# alphanewt_v1_5.net
KiCad netlist of a schematic drawn in EAGLE
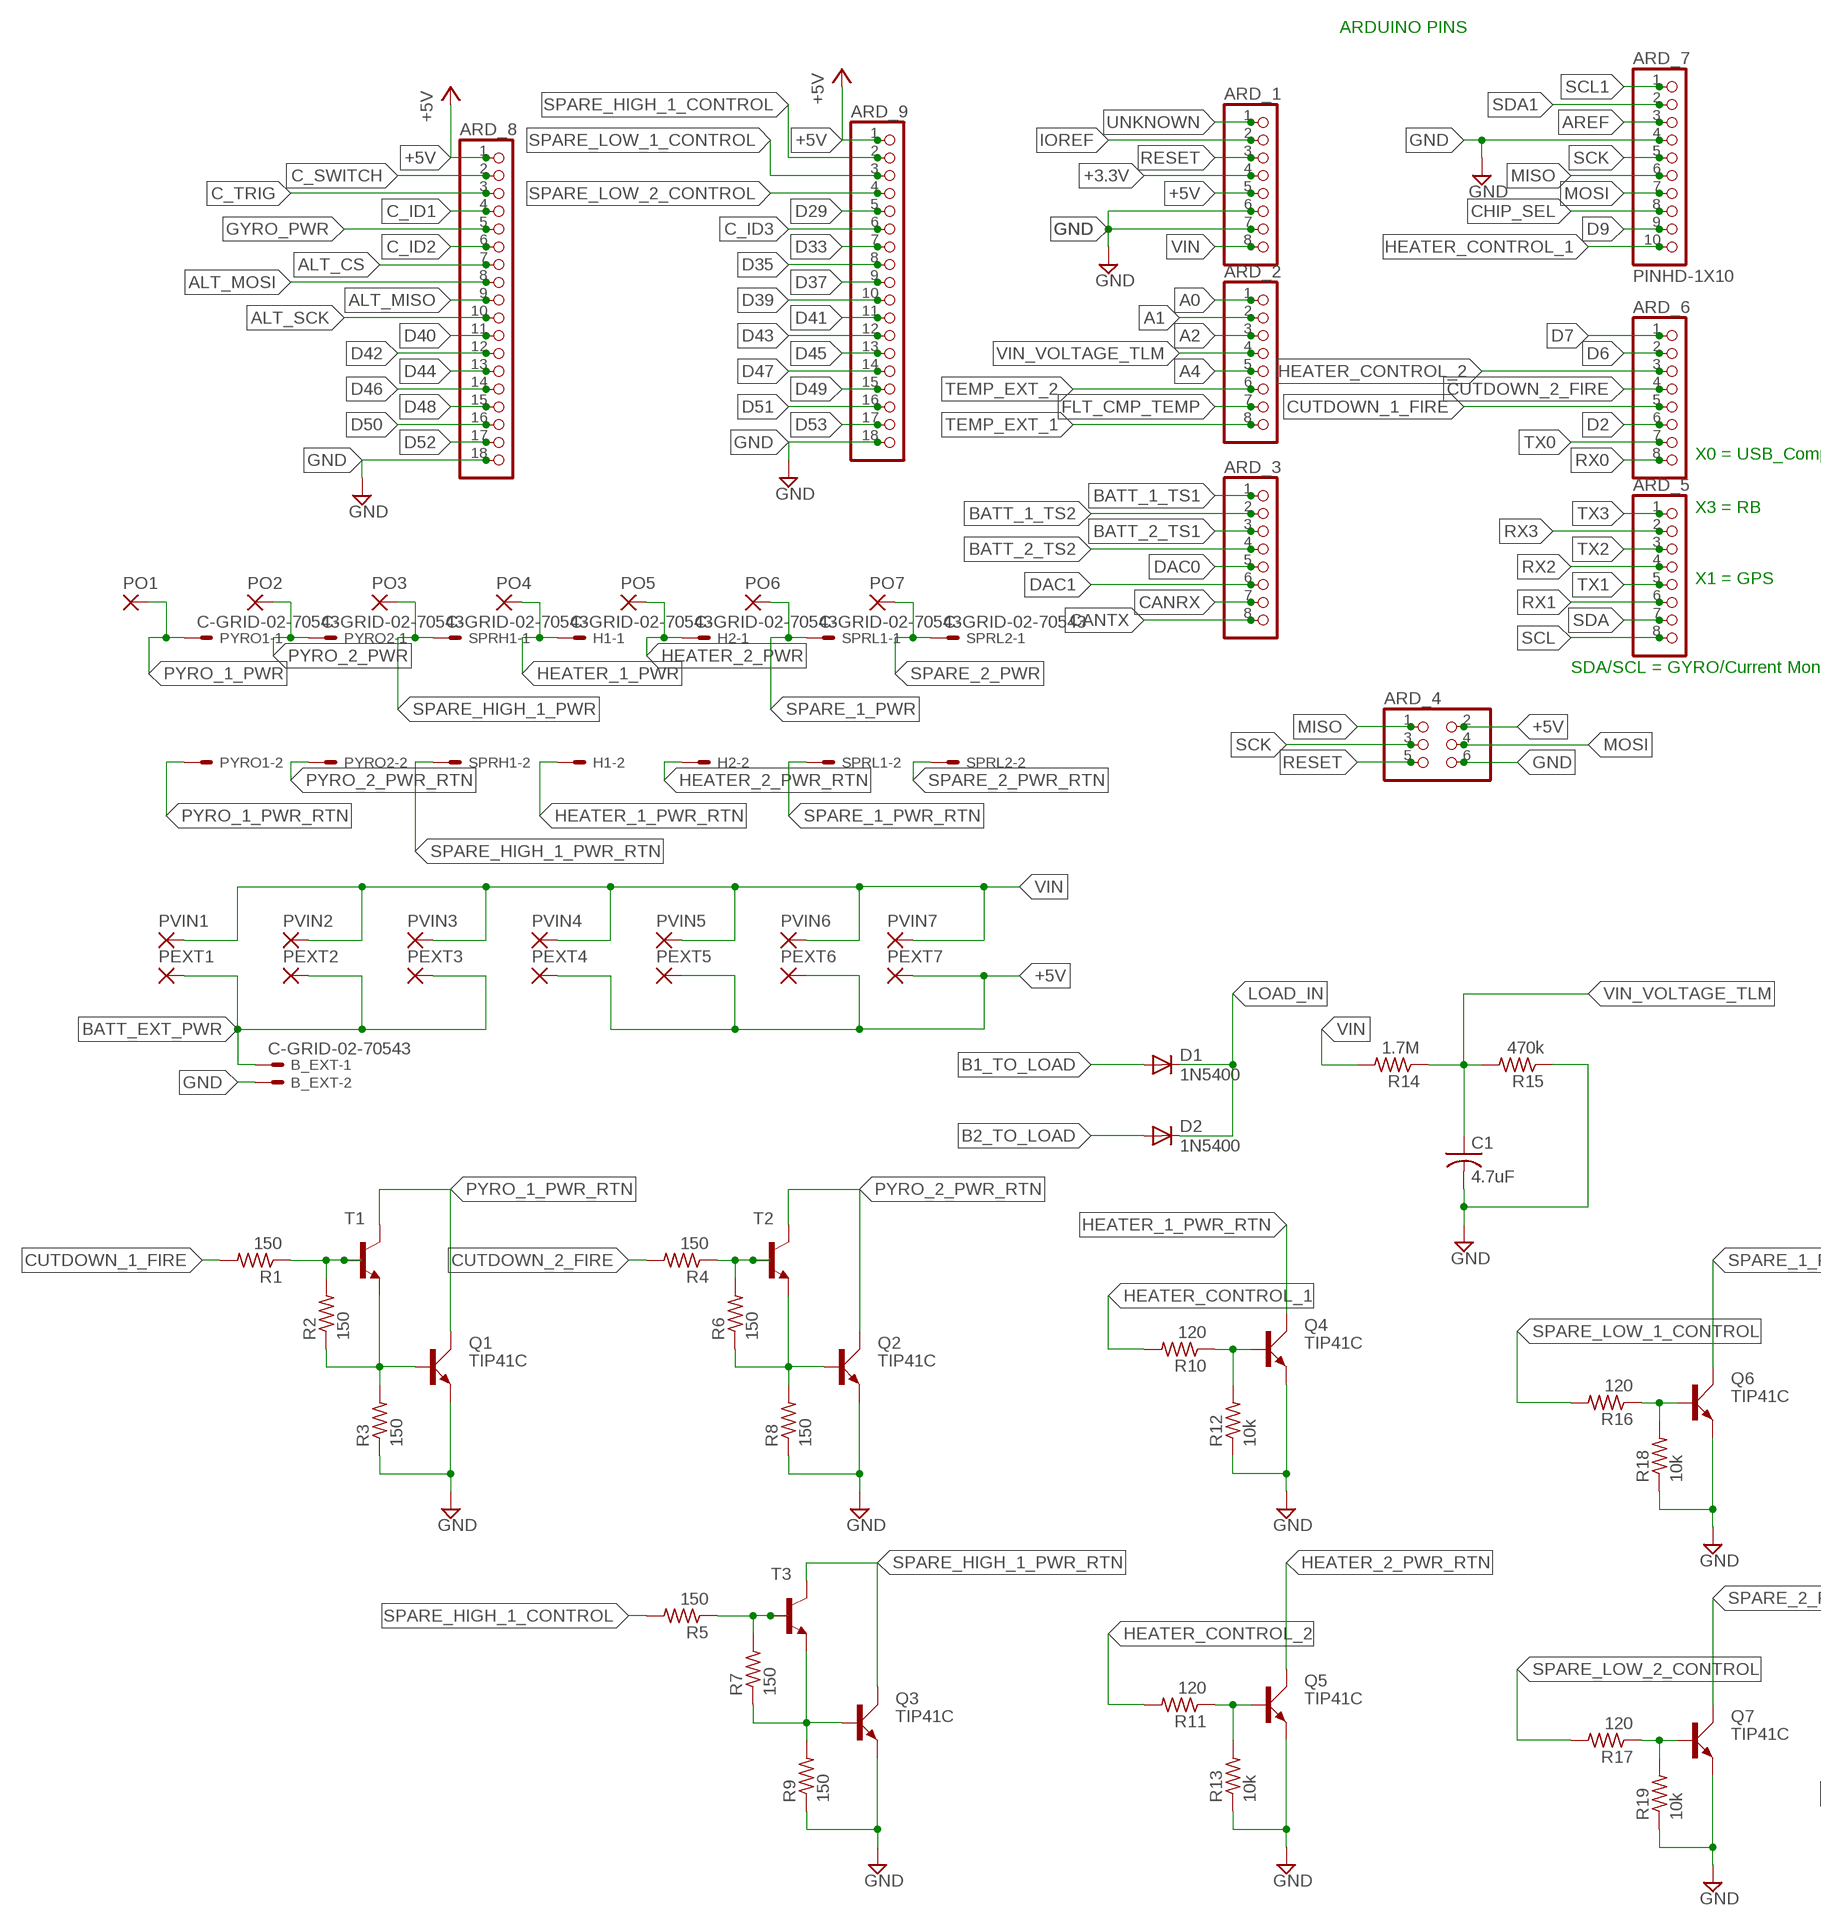
[diagram p0: schematic, sheet 1, part 1 of 2]
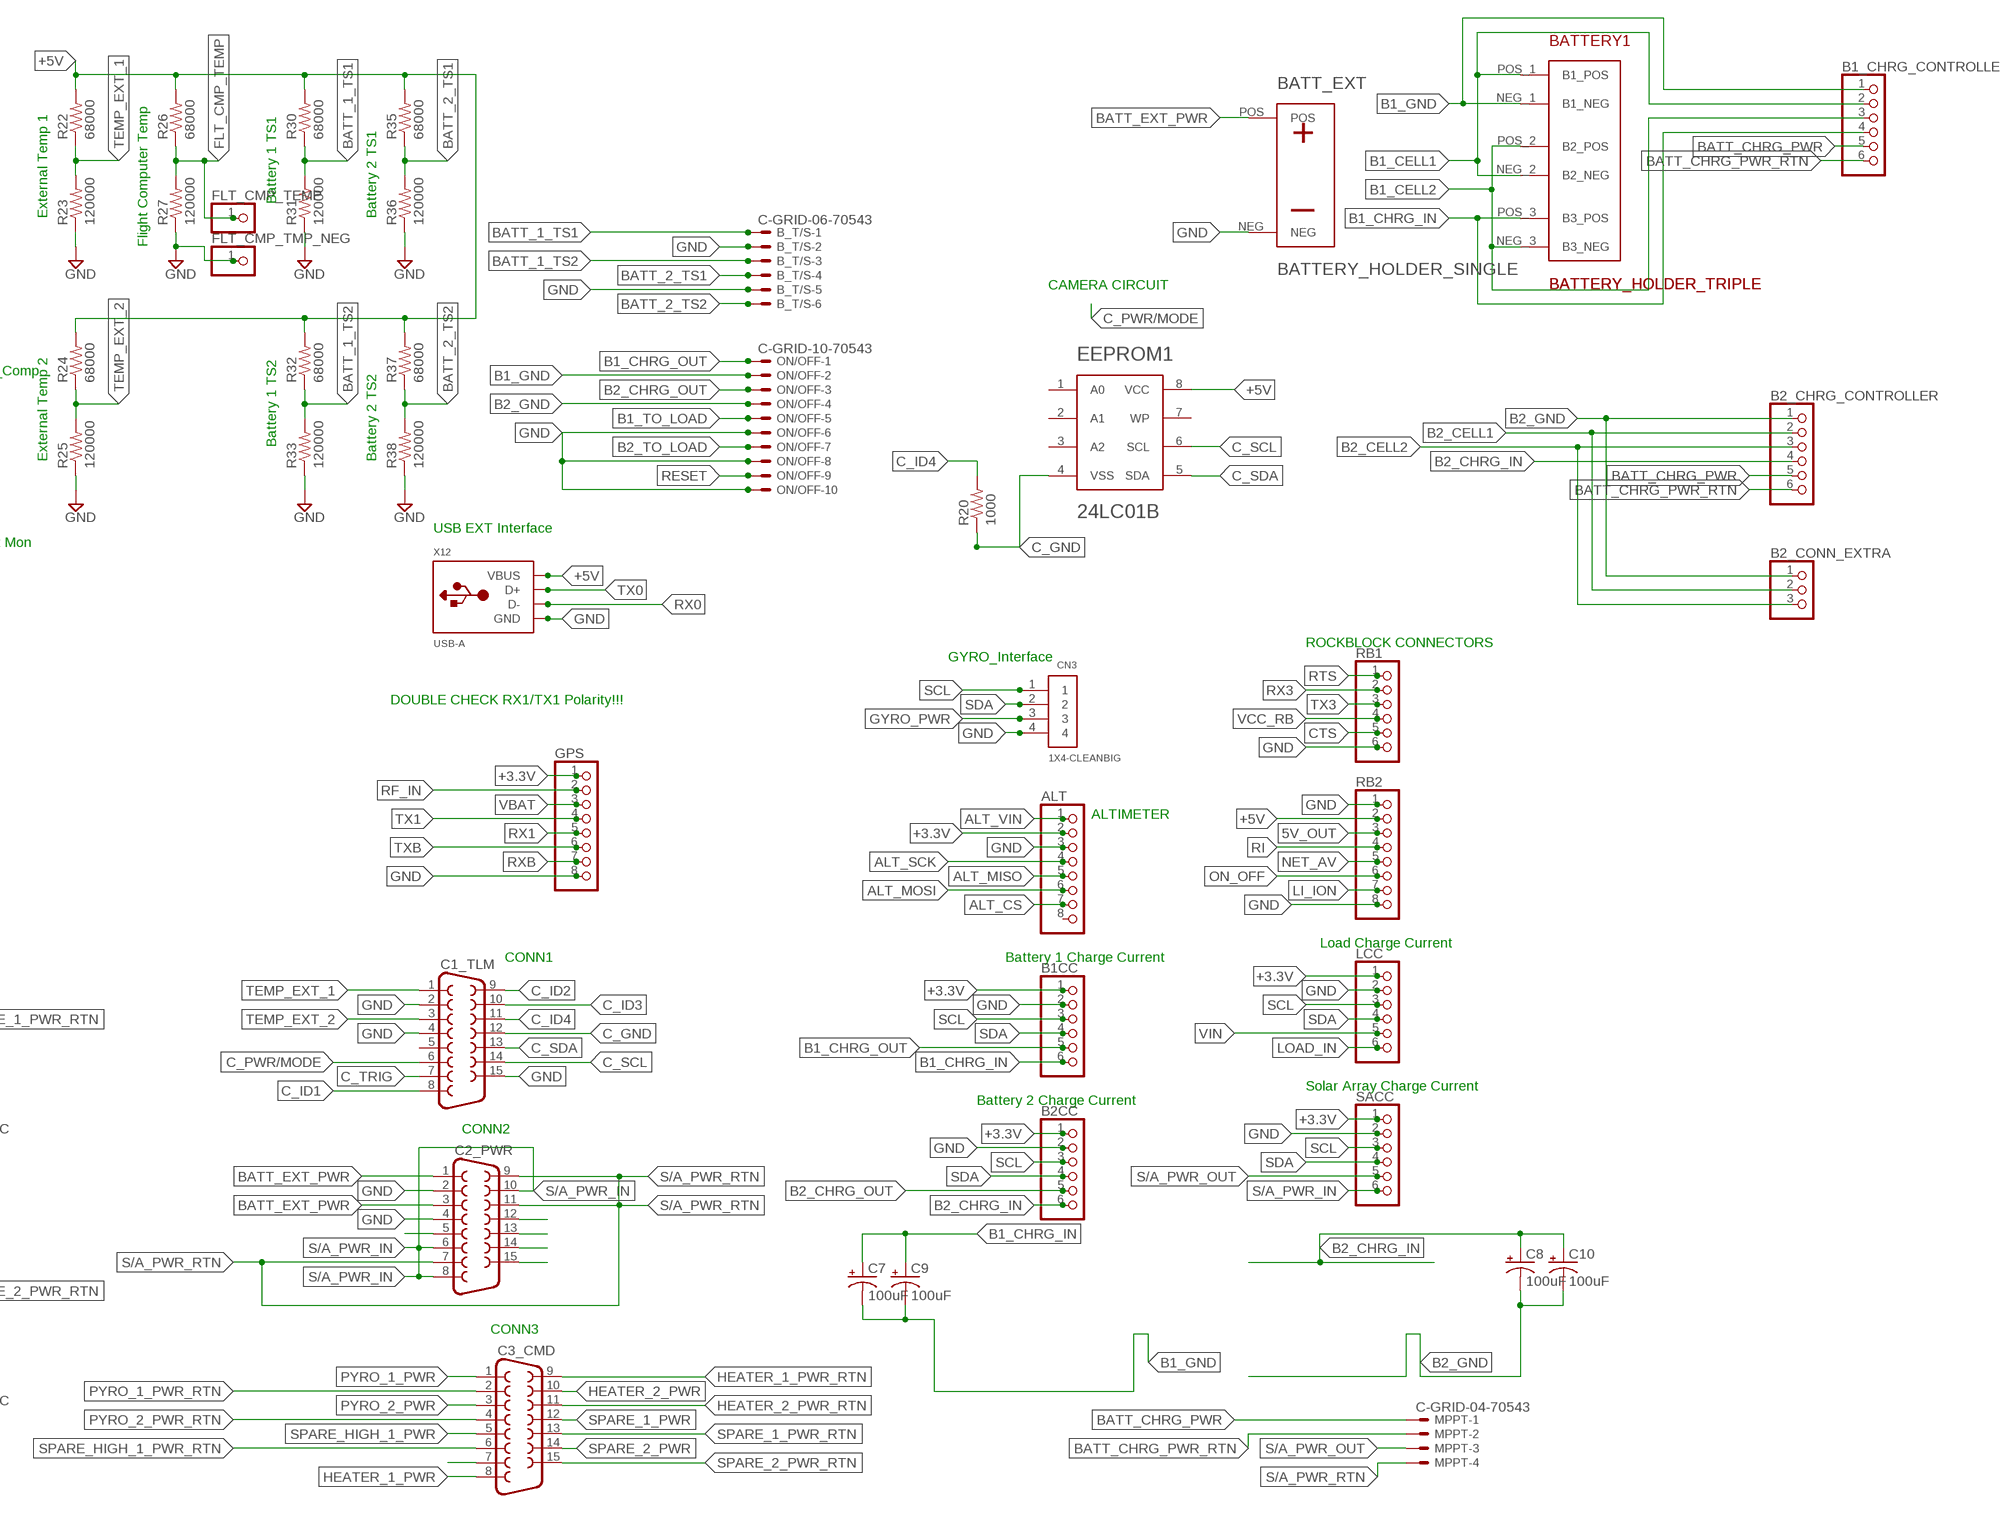
[diagram p1: schematic, sheet 1, part 2 of 2]

(export (version "E")
  (design (tool "Eeschema 10.0.6"))
  (components
    (comp (ref "ALT")
      (value "PINHD-1X8BIG")
      (footprint "eagle-import:1X08-BIG")
      (libsource (lib "eagle-import") (part "PINHD-1X8BIG"))
    )
    (comp (ref "ARD_1")
      (value "PINHD-1X8BIG")
      (footprint "eagle-import:1X08-BIG")
      (libsource (lib "eagle-import") (part "PINHD-1X8BIG"))
    )
    (comp (ref "ARD_2")
      (value "PINHD-1X8BIG")
      (footprint "eagle-import:1X08-BIG")
      (libsource (lib "eagle-import") (part "PINHD-1X8BIG"))
    )
    (comp (ref "ARD_3")
      (value "PINHD-1X8BIG")
      (footprint "eagle-import:1X08-BIG")
      (libsource (lib "eagle-import") (part "PINHD-1X8BIG"))
    )
    (comp (ref "ARD_4")
      (value "PINHD-2X3")
      (footprint "eagle-import:2X03")
      (libsource (lib "eagle-import") (part "PINHD-2X3"))
    )
    (comp (ref "ARD_5")
      (value "PINHD-1X8BIG")
      (footprint "eagle-import:1X08-BIG")
      (libsource (lib "eagle-import") (part "PINHD-1X8BIG"))
    )
    (comp (ref "ARD_6")
      (value "PINHD-1X8BIG")
      (footprint "eagle-import:1X08-BIG")
      (libsource (lib "eagle-import") (part "PINHD-1X8BIG"))
    )
    (comp (ref "ARD_7")
      (value "PINHD-1X10")
      (footprint "eagle-import:1X10-BIG")
      (libsource (lib "eagle-import") (part "PINHD-1X10"))
    )
    (comp (ref "ARD_8")
      (value "PINHD-1X18-BIG")
      (footprint "eagle-import:1X18-BIG")
      (libsource (lib "eagle-import") (part "PINHD-1X18-BIG"))
    )
    (comp (ref "ARD_9")
      (value "PINHD-1X18-BIG")
      (footprint "eagle-import:1X18-BIG")
      (libsource (lib "eagle-import") (part "PINHD-1X18-BIG"))
    )
    (comp (ref "B1CC")
      (value "PINHD-1X6B")
      (footprint "eagle-import:1X06-BIG")
      (libsource (lib "eagle-import") (part "PINHD-1X6B"))
    )
    (comp (ref "B1_CHRG_CONTROLLER")
      (value "PINHD-1X6CLEAN")
      (footprint "eagle-import:1X06-CLEAN")
      (libsource (lib "eagle-import") (part "PINHD-1X6CLEAN"))
    )
    (comp (ref "B2CC")
      (value "PINHD-1X6B")
      (footprint "eagle-import:1X06-BIG")
      (libsource (lib "eagle-import") (part "PINHD-1X6B"))
    )
    (comp (ref "B2_CHRG_CONTROLLER")
      (value "PINHD-1X6CLEAN")
      (footprint "eagle-import:1X06-CLEAN")
      (libsource (lib "eagle-import") (part "PINHD-1X6CLEAN"))
    )
    (comp (ref "B2_CONN_EXTRA")
      (value "PINHD-1X3CB")
      (footprint "eagle-import:1X03-CLEANBIG")
      (libsource (lib "eagle-import") (part "PINHD-1X3CB"))
    )
    (comp (ref "BATTERY1")
      (value "BATTERY_HOLDER_TRIPLE")
      (footprint "eagle-import:BATT_HOLDER_SINGLE")
      (libsource (lib "eagle-import") (part "BATTERY_HOLDER_TRIPLE"))
    )
    (comp (ref "BATT_EXT")
      (value "BATTERY_HOLDER_SINGLE")
      (footprint "eagle-import:BATT_HOLDER_SINGLE")
      (libsource (lib "eagle-import") (part "BATTERY_HOLDER_SINGLE"))
    )
    (comp (ref "B_EXT")
      (value "C-GRID-02-70543")
      (footprint "eagle-import:70543-02")
      (fields
        (field (name "MF") "MOLEX")
        (field (name "MPN") "70543-0001")
        (field (name "OC_NEWARK") "59H2645")
      )
      (libsource (lib "eagle-import") (part "C-GRID-02-70543"))
    )
    (comp (ref "B_T/S")
      (value "C-GRID-06-70543")
      (footprint "eagle-import:70543-06")
      (fields
        (field (name "MF") "MOLEX")
        (field (name "MPN") "70543-0005")
        (field (name "OC_NEWARK") "59H2647")
      )
      (libsource (lib "eagle-import") (part "C-GRID-06-70543"))
    )
    (comp (ref "C1")
      (value "4.7uF")
      (footprint "eagle-import:C0805K")
      (fields (field (name "MPN") "C2012X6S1H475K125AC"))
      (libsource (lib "eagle-import") (part "C-USC0805K"))
    )
    (comp (ref "C1_TLM")
      (value "F15HP")
      (footprint "eagle-import:F15HP")
      (fields (field (name "MPN") "5504F1-15S-02A-03"))
      (libsource (lib "eagle-import") (part "F15HP"))
    )
    (comp (ref "C2_PWR")
      (value "F15HP")
      (footprint "eagle-import:F15HP")
      (fields (field (name "MPN") "5504F1-15S-02A-03"))
      (libsource (lib "eagle-import") (part "F15HP"))
    )
    (comp (ref "C3_CMD")
      (value "F15HP")
      (footprint "eagle-import:F15HP")
      (fields (field (name "MPN") "5504F1-15S-02A-03"))
      (libsource (lib "eagle-import") (part "F15HP"))
    )
    (comp (ref "C7")
      (value "100uF")
      (footprint "eagle-import:CT7343")
      (fields (field (name "MPN") "TCN4337M020R0100"))
      (libsource (lib "eagle-import") (part "CPOL-USCT7343"))
    )
    (comp (ref "C8")
      (value "100uF")
      (footprint "eagle-import:CT7343")
      (fields (field (name "MPN") "TCN4337M020R0100"))
      (libsource (lib "eagle-import") (part "CPOL-USCT7343"))
    )
    (comp (ref "C9")
      (value "100uF")
      (footprint "eagle-import:CT7343")
      (fields (field (name "MPN") "TCN4337M020R0100"))
      (libsource (lib "eagle-import") (part "CPOL-USCT7343"))
    )
    (comp (ref "C10")
      (value "100uF")
      (footprint "eagle-import:CT7343")
      (fields (field (name "MPN") "TCN4337M020R0100"))
      (libsource (lib "eagle-import") (part "CPOL-USCT7343"))
    )
    (comp (ref "CN3")
      (value "1X4-CLEANBIG")
      (footprint "eagle-import:1X04-CLEANBIG")
      (libsource (lib "eagle-import") (part "1X4-CLEANBIG"))
    )
    (comp (ref "D1")
      (value "1N5400")
      (footprint "eagle-import:DO201-15")
      (fields (field (name "MPN") "1N5400-E3/54"))
      (libsource (lib "eagle-import") (part "1N5400"))
    )
    (comp (ref "D2")
      (value "1N5400")
      (footprint "eagle-import:DO201-15")
      (fields (field (name "MPN") "1N5400-E3/54"))
      (libsource (lib "eagle-import") (part "1N5400"))
    )
    (comp (ref "EEPROM1")
      (value "24LC01B")
      (footprint "eagle-import:SOP65P490X110-8N")
      (libsource (lib "eagle-import") (part "24LC01B"))
    )
    (comp (ref "FLT_CMP_TEMP")
      (value "PINHD-1X1")
      (footprint "eagle-import:1X01")
      (libsource (lib "eagle-import") (part "PINHD-1X1"))
    )
    (comp (ref "FLT_CMP_TMP_NEG")
      (value "PINHD-1X1")
      (footprint "eagle-import:1X01")
      (libsource (lib "eagle-import") (part "PINHD-1X1"))
    )
    (comp (ref "GPS")
      (value "PINHD-1X8BIG")
      (footprint "eagle-import:1X08-BIG")
      (libsource (lib "eagle-import") (part "PINHD-1X8BIG"))
    )
    (comp (ref "H1")
      (value "C-GRID-02-70543")
      (footprint "eagle-import:70543-02")
      (fields
        (field (name "MF") "MOLEX")
        (field (name "MPN") "70543-0001")
        (field (name "OC_NEWARK") "59H2645")
      )
      (libsource (lib "eagle-import") (part "C-GRID-02-70543"))
    )
    (comp (ref "H2")
      (value "C-GRID-02-70543")
      (footprint "eagle-import:70543-02")
      (fields
        (field (name "MF") "MOLEX")
        (field (name "MPN") "70543-0001")
        (field (name "OC_NEWARK") "59H2645")
      )
      (libsource (lib "eagle-import") (part "C-GRID-02-70543"))
    )
    (comp (ref "LCC")
      (value "PINHD-1X6B")
      (footprint "eagle-import:1X06-BIG")
      (libsource (lib "eagle-import") (part "PINHD-1X6B"))
    )
    (comp (ref "MPPT")
      (value "C-GRID-04-70543")
      (footprint "eagle-import:70543-04")
      (fields
        (field (name "MF") "MOLEX")
        (field (name "MPN") "70543-0038")
        (field (name "OC_NEWARK") "59H2665")
      )
      (libsource (lib "eagle-import") (part "C-GRID-04-70543"))
    )
    (comp (ref "ON/OFF")
      (value "C-GRID-10-70543")
      (footprint "eagle-import:70543-10")
      (fields
        (field (name "MF") "MOLEX")
        (field (name "MPN") "70543-0009")
        (field (name "OC_NEWARK") "59H2651")
      )
      (libsource (lib "eagle-import") (part "C-GRID-10-70543"))
    )
    (comp (ref "PEXT1")
      (value "SMD2")
      (footprint "eagle-import:SMD1,27-2,54")
      (libsource (lib "eagle-import") (part "SMD2"))
    )
    (comp (ref "PEXT2")
      (value "SMD2")
      (footprint "eagle-import:SMD1,27-2,54")
      (libsource (lib "eagle-import") (part "SMD2"))
    )
    (comp (ref "PEXT3")
      (value "SMD2")
      (footprint "eagle-import:SMD1,27-2,54")
      (libsource (lib "eagle-import") (part "SMD2"))
    )
    (comp (ref "PEXT4")
      (value "SMD2")
      (footprint "eagle-import:SMD1,27-2,54")
      (libsource (lib "eagle-import") (part "SMD2"))
    )
    (comp (ref "PEXT5")
      (value "SMD2")
      (footprint "eagle-import:SMD1,27-2,54")
      (libsource (lib "eagle-import") (part "SMD2"))
    )
    (comp (ref "PEXT6")
      (value "SMD2")
      (footprint "eagle-import:SMD1,27-2,54")
      (libsource (lib "eagle-import") (part "SMD2"))
    )
    (comp (ref "PEXT7")
      (value "SMD2")
      (footprint "eagle-import:SMD1,27-2,54")
      (libsource (lib "eagle-import") (part "SMD2"))
    )
    (comp (ref "PO1")
      (value "SMD2")
      (footprint "eagle-import:SMD1,27-2,54")
      (libsource (lib "eagle-import") (part "SMD2"))
    )
    (comp (ref "PO2")
      (value "SMD2")
      (footprint "eagle-import:SMD1,27-2,54")
      (libsource (lib "eagle-import") (part "SMD2"))
    )
    (comp (ref "PO3")
      (value "SMD2")
      (footprint "eagle-import:SMD1,27-2,54")
      (libsource (lib "eagle-import") (part "SMD2"))
    )
    (comp (ref "PO4")
      (value "SMD2")
      (footprint "eagle-import:SMD1,27-2,54")
      (libsource (lib "eagle-import") (part "SMD2"))
    )
    (comp (ref "PO5")
      (value "SMD2")
      (footprint "eagle-import:SMD1,27-2,54")
      (libsource (lib "eagle-import") (part "SMD2"))
    )
    (comp (ref "PO6")
      (value "SMD2")
      (footprint "eagle-import:SMD1,27-2,54")
      (libsource (lib "eagle-import") (part "SMD2"))
    )
    (comp (ref "PO7")
      (value "SMD2")
      (footprint "eagle-import:SMD1,27-2,54")
      (libsource (lib "eagle-import") (part "SMD2"))
    )
    (comp (ref "PVIN1")
      (value "SMD2")
      (footprint "eagle-import:SMD1,27-2,54")
      (libsource (lib "eagle-import") (part "SMD2"))
    )
    (comp (ref "PVIN2")
      (value "SMD2")
      (footprint "eagle-import:SMD1,27-2,54")
      (libsource (lib "eagle-import") (part "SMD2"))
    )
    (comp (ref "PVIN3")
      (value "SMD2")
      (footprint "eagle-import:SMD1,27-2,54")
      (libsource (lib "eagle-import") (part "SMD2"))
    )
    (comp (ref "PVIN4")
      (value "SMD2")
      (footprint "eagle-import:SMD1,27-2,54")
      (libsource (lib "eagle-import") (part "SMD2"))
    )
    (comp (ref "PVIN5")
      (value "SMD2")
      (footprint "eagle-import:SMD1,27-2,54")
      (libsource (lib "eagle-import") (part "SMD2"))
    )
    (comp (ref "PVIN6")
      (value "SMD2")
      (footprint "eagle-import:SMD1,27-2,54")
      (libsource (lib "eagle-import") (part "SMD2"))
    )
    (comp (ref "PVIN7")
      (value "SMD2")
      (footprint "eagle-import:SMD1,27-2,54")
      (libsource (lib "eagle-import") (part "SMD2"))
    )
    (comp (ref "PYRO1")
      (value "C-GRID-02-70543")
      (footprint "eagle-import:70543-02")
      (fields
        (field (name "MF") "MOLEX")
        (field (name "MPN") "70543-0001")
        (field (name "OC_NEWARK") "59H2645")
      )
      (libsource (lib "eagle-import") (part "C-GRID-02-70543"))
    )
    (comp (ref "PYRO2")
      (value "C-GRID-02-70543")
      (footprint "eagle-import:70543-02")
      (fields
        (field (name "MF") "MOLEX")
        (field (name "MPN") "70543-0001")
        (field (name "OC_NEWARK") "59H2645")
      )
      (libsource (lib "eagle-import") (part "C-GRID-02-70543"))
    )
    (comp (ref "Q1")
      (value "TIP41C")
      (footprint "eagle-import:TO220AV")
      (fields (field (name "MF") "FAIRCHILD SEMICONDUCTOR"))
      (libsource (lib "eagle-import") (part "TIP41C"))
    )
    (comp (ref "Q2")
      (value "TIP41C")
      (footprint "eagle-import:TO220AV")
      (fields (field (name "MF") "FAIRCHILD SEMICONDUCTOR"))
      (libsource (lib "eagle-import") (part "TIP41C"))
    )
    (comp (ref "Q3")
      (value "TIP41C")
      (footprint "eagle-import:TO220AV")
      (fields (field (name "MF") "FAIRCHILD SEMICONDUCTOR"))
      (libsource (lib "eagle-import") (part "TIP41C"))
    )
    (comp (ref "Q4")
      (value "TIP41C")
      (footprint "eagle-import:TO220AV")
      (fields (field (name "MF") "FAIRCHILD SEMICONDUCTOR"))
      (libsource (lib "eagle-import") (part "TIP41C"))
    )
    (comp (ref "Q5")
      (value "TIP41C")
      (footprint "eagle-import:TO220AV")
      (fields (field (name "MF") "FAIRCHILD SEMICONDUCTOR"))
      (libsource (lib "eagle-import") (part "TIP41C"))
    )
    (comp (ref "Q6")
      (value "TIP41C")
      (footprint "eagle-import:TO220AV")
      (fields (field (name "MF") "FAIRCHILD SEMICONDUCTOR"))
      (libsource (lib "eagle-import") (part "TIP41C"))
    )
    (comp (ref "Q7")
      (value "TIP41C")
      (footprint "eagle-import:TO220AV")
      (fields (field (name "MF") "FAIRCHILD SEMICONDUCTOR"))
      (libsource (lib "eagle-import") (part "TIP41C"))
    )
    (comp (ref "R1")
      (value "150")
      (footprint "eagle-import:R0805")
      (fields (field (name "MF") "VISHAY/DALE") (field (name "MPN") "CRCW120633R2FKEA"))
      (libsource (lib "eagle-import") (part "R-US_R0805"))
    )
    (comp (ref "R2")
      (value "150")
      (footprint "eagle-import:R0805")
      (fields (field (name "MF") "VISHAY/DALE") (field (name "MPN") "CRCW120633R2FKEA"))
      (libsource (lib "eagle-import") (part "R-US_R0805"))
    )
    (comp (ref "R3")
      (value "150")
      (footprint "eagle-import:R0805")
      (fields (field (name "MF") "VISHAY/DALE") (field (name "MPN") "CRCW120633R2FKEA"))
      (libsource (lib "eagle-import") (part "R-US_R0805"))
    )
    (comp (ref "R4")
      (value "150")
      (footprint "eagle-import:R0805")
      (fields (field (name "MF") "VISHAY/DALE") (field (name "MPN") "CRCW120633R2FKEA"))
      (libsource (lib "eagle-import") (part "R-US_R0805"))
    )
    (comp (ref "R5")
      (value "150")
      (footprint "eagle-import:R0805")
      (fields (field (name "MF") "VISHAY/DALE") (field (name "MPN") "CRCW120633R2FKEA"))
      (libsource (lib "eagle-import") (part "R-US_R0805"))
    )
    (comp (ref "R6")
      (value "150")
      (footprint "eagle-import:R0805")
      (fields (field (name "MF") "VISHAY/DALE") (field (name "MPN") "CRCW120633R2FKEA"))
      (libsource (lib "eagle-import") (part "R-US_R0805"))
    )
    (comp (ref "R7")
      (value "150")
      (footprint "eagle-import:R0805")
      (fields (field (name "MF") "VISHAY/DALE") (field (name "MPN") "CRCW120633R2FKEA"))
      (libsource (lib "eagle-import") (part "R-US_R0805"))
    )
    (comp (ref "R8")
      (value "150")
      (footprint "eagle-import:R0805")
      (fields (field (name "MF") "VISHAY/DALE") (field (name "MPN") "CRCW120633R2FKEA"))
      (libsource (lib "eagle-import") (part "R-US_R0805"))
    )
    (comp (ref "R9")
      (value "150")
      (footprint "eagle-import:R0805")
      (fields (field (name "MF") "VISHAY/DALE") (field (name "MPN") "CRCW120633R2FKEA"))
      (libsource (lib "eagle-import") (part "R-US_R0805"))
    )
    (comp (ref "R10")
      (value "120")
      (footprint "eagle-import:R0805")
      (fields (field (name "MF") "VISHAY/DALE") (field (name "MPN") "CRCW120633R2FKEA"))
      (libsource (lib "eagle-import") (part "R-US_R0805"))
    )
    (comp (ref "R11")
      (value "120")
      (footprint "eagle-import:R0805")
      (fields (field (name "MF") "VISHAY/DALE") (field (name "MPN") "CRCW120633R2FKEA"))
      (libsource (lib "eagle-import") (part "R-US_R0805"))
    )
    (comp (ref "R12")
      (value "10k")
      (footprint "eagle-import:R0805")
      (fields (field (name "MF") "VISHAY/DALE") (field (name "MPN") "CRCW120633R2FKEA"))
      (libsource (lib "eagle-import") (part "R-US_R0805"))
    )
    (comp (ref "R13")
      (value "10k")
      (footprint "eagle-import:R0805")
      (fields (field (name "MF") "VISHAY/DALE") (field (name "MPN") "CRCW120633R2FKEA"))
      (libsource (lib "eagle-import") (part "R-US_R0805"))
    )
    (comp (ref "R14")
      (value "1.7M")
      (footprint "eagle-import:R0805")
      (fields (field (name "MF") "VISHAY/DALE") (field (name "MPN") "CRCW120633R2FKEA"))
      (libsource (lib "eagle-import") (part "R-US_R0805"))
    )
    (comp (ref "R15")
      (value "470k")
      (footprint "eagle-import:R0805")
      (fields (field (name "MF") "VISHAY/DALE") (field (name "MPN") "CRCW120633R2FKEA"))
      (libsource (lib "eagle-import") (part "R-US_R0805"))
    )
    (comp (ref "R16")
      (value "120")
      (footprint "eagle-import:R0805")
      (fields (field (name "MF") "VISHAY/DALE") (field (name "MPN") "CRCW120633R2FKEA"))
      (libsource (lib "eagle-import") (part "R-US_R0805"))
    )
    (comp (ref "R17")
      (value "120")
      (footprint "eagle-import:R0805")
      (fields (field (name "MF") "VISHAY/DALE") (field (name "MPN") "CRCW120633R2FKEA"))
      (libsource (lib "eagle-import") (part "R-US_R0805"))
    )
    (comp (ref "R18")
      (value "10k")
      (footprint "eagle-import:R0805")
      (fields (field (name "MF") "VISHAY/DALE") (field (name "MPN") "CRCW120633R2FKEA"))
      (libsource (lib "eagle-import") (part "R-US_R0805"))
    )
    (comp (ref "R19")
      (value "10k")
      (footprint "eagle-import:R0805")
      (fields (field (name "MF") "VISHAY/DALE") (field (name "MPN") "CRCW120633R2FKEA"))
      (libsource (lib "eagle-import") (part "R-US_R0805"))
    )
    (comp (ref "R20")
      (value "1000")
      (footprint "eagle-import:R0805")
      (fields (field (name "MF") "VISHAY/DALE") (field (name "MPN") "CRCW120633R2FKEA"))
      (libsource (lib "eagle-import") (part "R-US_R0805"))
    )
    (comp (ref "R22")
      (value "68000")
      (footprint "eagle-import:R0805")
      (fields (field (name "MF") "VISHAY/DALE") (field (name "MPN") "CRCW120633R2FKEA"))
      (libsource (lib "eagle-import") (part "R-US_R0805"))
    )
    (comp (ref "R23")
      (value "120000")
      (footprint "eagle-import:R0805")
      (fields (field (name "MF") "VISHAY/DALE") (field (name "MPN") "CRCW120633R2FKEA"))
      (libsource (lib "eagle-import") (part "R-US_R0805"))
    )
    (comp (ref "R24")
      (value "68000")
      (footprint "eagle-import:R0805")
      (fields (field (name "MF") "VISHAY/DALE") (field (name "MPN") "CRCW120633R2FKEA"))
      (libsource (lib "eagle-import") (part "R-US_R0805"))
    )
    (comp (ref "R25")
      (value "120000")
      (footprint "eagle-import:R0805")
      (fields (field (name "MF") "VISHAY/DALE") (field (name "MPN") "CRCW120633R2FKEA"))
      (libsource (lib "eagle-import") (part "R-US_R0805"))
    )
    (comp (ref "R26")
      (value "68000")
      (footprint "eagle-import:R0805")
      (fields (field (name "MF") "VISHAY/DALE") (field (name "MPN") "CRCW120633R2FKEA"))
      (libsource (lib "eagle-import") (part "R-US_R0805"))
    )
    (comp (ref "R27")
      (value "120000")
      (footprint "eagle-import:R0805")
      (fields (field (name "MF") "VISHAY/DALE") (field (name "MPN") "CRCW120633R2FKEA"))
      (libsource (lib "eagle-import") (part "R-US_R0805"))
    )
    (comp (ref "R30")
      (value "68000")
      (footprint "eagle-import:R0805")
      (fields (field (name "MF") "VISHAY/DALE") (field (name "MPN") "CRCW120633R2FKEA"))
      (libsource (lib "eagle-import") (part "R-US_R0805"))
    )
    (comp (ref "R31")
      (value "120000")
      (footprint "eagle-import:R0805")
      (fields (field (name "MF") "VISHAY/DALE") (field (name "MPN") "CRCW120633R2FKEA"))
      (libsource (lib "eagle-import") (part "R-US_R0805"))
    )
    (comp (ref "R32")
      (value "68000")
      (footprint "eagle-import:R0805")
      (fields (field (name "MF") "VISHAY/DALE") (field (name "MPN") "CRCW120633R2FKEA"))
      (libsource (lib "eagle-import") (part "R-US_R0805"))
    )
    (comp (ref "R33")
      (value "120000")
      (footprint "eagle-import:R0805")
      (fields (field (name "MF") "VISHAY/DALE") (field (name "MPN") "CRCW120633R2FKEA"))
      (libsource (lib "eagle-import") (part "R-US_R0805"))
    )
    (comp (ref "R35")
      (value "68000")
      (footprint "eagle-import:R0805")
      (fields (field (name "MF") "VISHAY/DALE") (field (name "MPN") "CRCW120633R2FKEA"))
      (libsource (lib "eagle-import") (part "R-US_R0805"))
    )
    (comp (ref "R36")
      (value "120000")
      (footprint "eagle-import:R0805")
      (fields (field (name "MF") "VISHAY/DALE") (field (name "MPN") "CRCW120633R2FKEA"))
      (libsource (lib "eagle-import") (part "R-US_R0805"))
    )
    (comp (ref "R37")
      (value "68000")
      (footprint "eagle-import:R0805")
      (fields (field (name "MF") "VISHAY/DALE") (field (name "MPN") "CRCW120633R2FKEA"))
      (libsource (lib "eagle-import") (part "R-US_R0805"))
    )
    (comp (ref "R38")
      (value "120000")
      (footprint "eagle-import:R0805")
      (fields (field (name "MF") "VISHAY/DALE") (field (name "MPN") "CRCW120633R2FKEA"))
      (libsource (lib "eagle-import") (part "R-US_R0805"))
    )
    (comp (ref "RB1")
      (value "PINHD-1X6CB")
      (footprint "eagle-import:1X06-CLEANBIG")
      (libsource (lib "eagle-import") (part "PINHD-1X6CB"))
    )
    (comp (ref "RB2")
      (value "PINHD-1X8BIG")
      (footprint "eagle-import:1X08-BIG")
      (libsource (lib "eagle-import") (part "PINHD-1X8BIG"))
    )
    (comp (ref "SACC")
      (value "PINHD-1X6B")
      (footprint "eagle-import:1X06-BIG")
      (libsource (lib "eagle-import") (part "PINHD-1X6B"))
    )
    (comp (ref "SPRH1")
      (value "C-GRID-02-70543")
      (footprint "eagle-import:70543-02")
      (fields
        (field (name "MF") "MOLEX")
        (field (name "MPN") "70543-0001")
        (field (name "OC_NEWARK") "59H2645")
      )
      (libsource (lib "eagle-import") (part "C-GRID-02-70543"))
    )
    (comp (ref "SPRL1")
      (value "C-GRID-02-70543")
      (footprint "eagle-import:70543-02")
      (fields
        (field (name "MF") "MOLEX")
        (field (name "MPN") "70543-0001")
        (field (name "OC_NEWARK") "59H2645")
      )
      (libsource (lib "eagle-import") (part "C-GRID-02-70543"))
    )
    (comp (ref "SPRL2")
      (value "C-GRID-02-70543")
      (footprint "eagle-import:70543-02")
      (fields
        (field (name "MF") "MOLEX")
        (field (name "MPN") "70543-0001")
        (field (name "OC_NEWARK") "59H2645")
      )
      (libsource (lib "eagle-import") (part "C-GRID-02-70543"))
    )
    (comp (ref "T1")
      (value "2N3904")
      (footprint "eagle-import:TO92")
      (fields (field (name "MF") "NTE ELECTRONICS"))
      (libsource (lib "eagle-import") (part "2N3904"))
    )
    (comp (ref "T2")
      (value "2N3904")
      (footprint "eagle-import:TO92")
      (fields (field (name "MF") "NTE ELECTRONICS"))
      (libsource (lib "eagle-import") (part "2N3904"))
    )
    (comp (ref "T3")
      (value "2N3904")
      (footprint "eagle-import:TO92")
      (fields (field (name "MF") "NTE ELECTRONICS"))
      (libsource (lib "eagle-import") (part "2N3904"))
    )
    (comp (ref "X12")
      (value "USB-A")
      (footprint "eagle-import:MOLEX_480371000")
      (fields (field (name "MPN") "UE27-AC54-10H"))
      (libsource (lib "eagle-import") (part "USB-A"))
    )
  )
  (nets
    (net (code "1") (name "+3.3V") (class "Default")
      (node (ref "ALT") (pin "2") (pinfunction "2_2") (pintype "passive"))
      (node (ref "ARD_1") (pin "4") (pinfunction "4_4") (pintype "passive"))
      (node (ref "B1CC") (pin "1") (pinfunction "1_1") (pintype "passive"))
      (node (ref "B2CC") (pin "1") (pinfunction "1_1") (pintype "passive"))
      (node (ref "GPS") (pin "1") (pinfunction "1_1") (pintype "passive"))
      (node (ref "LCC") (pin "1") (pinfunction "1_1") (pintype "passive"))
      (node (ref "SACC") (pin "1") (pinfunction "1_1") (pintype "passive"))
    )
    (net (code "2") (name "+5V") (class "Default")
      (node (ref "ARD_1") (pin "5") (pinfunction "5_5") (pintype "passive"))
      (node (ref "ARD_4") (pin "2") (pinfunction "2_2") (pintype "passive"))
      (node (ref "ARD_8") (pin "1") (pinfunction "1_1") (pintype "passive"))
      (node (ref "ARD_9") (pin "1") (pinfunction "1_1") (pintype "passive"))
      (node (ref "EEPROM1") (pin "8") (pinfunction "VCC_8") (pintype "bidirectional"))
      (node (ref "PEXT4") (pin "1") (pinfunction "P_1") (pintype "passive"))
      (node (ref "PEXT5") (pin "1") (pinfunction "P_1") (pintype "passive"))
      (node (ref "PEXT6") (pin "1") (pinfunction "P_1") (pintype "passive"))
      (node (ref "PEXT7") (pin "1") (pinfunction "P_1") (pintype "passive"))
      (node (ref "R22") (pin "2") (pinfunction "2_2") (pintype "passive"))
      (node (ref "R24") (pin "2") (pinfunction "2_2") (pintype "passive"))
      (node (ref "R26") (pin "2") (pinfunction "2_2") (pintype "passive"))
      (node (ref "R30") (pin "2") (pinfunction "2_2") (pintype "passive"))
      (node (ref "R32") (pin "2") (pinfunction "2_2") (pintype "passive"))
      (node (ref "R35") (pin "2") (pinfunction "2_2") (pintype "passive"))
      (node (ref "R37") (pin "2") (pinfunction "2_2") (pintype "passive"))
      (node (ref "RB2") (pin "2") (pinfunction "2_2") (pintype "passive"))
      (node (ref "X12") (pin "1") (pinfunction "VBUS_1") (pintype "power_in"))
    )
    (net (code "3") (name "5V_OUT") (class "Default")
      (node (ref "RB2") (pin "3") (pinfunction "3_3") (pintype "passive"))
    )
    (net (code "4") (name "A0") (class "Default")
      (node (ref "ARD_2") (pin "1") (pinfunction "1_1") (pintype "passive"))
    )
    (net (code "5") (name "A1") (class "Default")
      (node (ref "ARD_2") (pin "2") (pinfunction "2_2") (pintype "passive"))
    )
    (net (code "6") (name "A2") (class "Default")
      (node (ref "ARD_2") (pin "3") (pinfunction "3_3") (pintype "passive"))
    )
    (net (code "7") (name "A4") (class "Default")
      (node (ref "ARD_2") (pin "5") (pinfunction "5_5") (pintype "passive"))
    )
    (net (code "8") (name "ALT_CS") (class "Default")
      (node (ref "ALT") (pin "7") (pinfunction "7_7") (pintype "passive"))
      (node (ref "ARD_8") (pin "7") (pinfunction "7_7") (pintype "passive"))
    )
    (net (code "9") (name "ALT_MISO") (class "Default")
      (node (ref "ALT") (pin "5") (pinfunction "5_5") (pintype "passive"))
      (node (ref "ARD_8") (pin "9") (pinfunction "9_9") (pintype "passive"))
    )
    (net (code "10") (name "ALT_MOSI") (class "Default")
      (node (ref "ALT") (pin "6") (pinfunction "6_6") (pintype "passive"))
      (node (ref "ARD_8") (pin "8") (pinfunction "8_8") (pintype "passive"))
    )
    (net (code "11") (name "ALT_SCK") (class "Default")
      (node (ref "ALT") (pin "4") (pinfunction "4_4") (pintype "passive"))
      (node (ref "ARD_8") (pin "10") (pinfunction "10_10") (pintype "passive"))
    )
    (net (code "12") (name "ALT_VIN") (class "Default")
      (node (ref "ALT") (pin "1") (pinfunction "1_1") (pintype "passive"))
    )
    (net (code "13") (name "AREF") (class "Default")
      (node (ref "ARD_7") (pin "3") (pinfunction "3_3") (pintype "passive"))
    )
    (net (code "14") (name "B1_CELL1") (class "Default")
      (node (ref "B1_CHRG_CONTROLLER") (pin "2") (pinfunction "2_2") (pintype "passive"))
      (node (ref "BATTERY1") (pin "NEG_2") (pinfunction "B2_NEG_NEG_2") (pintype "bidirectional"))
      (node (ref "BATTERY1") (pin "POS_1") (pinfunction "B1_POS_POS_1") (pintype "bidirectional"))
    )
    (net (code "15") (name "B1_CELL2") (class "Default")
      (node (ref "B1_CHRG_CONTROLLER") (pin "3") (pinfunction "3_3") (pintype "passive"))
      (node (ref "BATTERY1") (pin "NEG_3") (pinfunction "B3_NEG_NEG_3") (pintype "bidirectional"))
      (node (ref "BATTERY1") (pin "POS_2") (pinfunction "B2_POS_POS_2") (pintype "bidirectional"))
    )
    (net (code "16") (name "B1_CHRG_IN") (class "Default")
      (node (ref "B1CC") (pin "6") (pinfunction "6_6") (pintype "passive"))
      (node (ref "B1_CHRG_CONTROLLER") (pin "4") (pinfunction "4_4") (pintype "passive"))
      (node (ref "BATTERY1") (pin "POS_3") (pinfunction "B3_POS_POS_3") (pintype "bidirectional"))
      (node (ref "C7") (pin "+") (pinfunction "+_+") (pintype "passive"))
      (node (ref "C9") (pin "+") (pinfunction "+_+") (pintype "passive"))
    )
    (net (code "17") (name "B1_CHRG_OUT") (class "Default")
      (node (ref "B1CC") (pin "5") (pinfunction "5_5") (pintype "passive"))
      (node (ref "ON/OFF") (pin "1") (pinfunction "S_1") (pintype "passive"))
    )
    (net (code "18") (name "B1_GND") (class "Default")
      (node (ref "B1_CHRG_CONTROLLER") (pin "1") (pinfunction "1_1") (pintype "passive"))
      (node (ref "BATTERY1") (pin "NEG_1") (pinfunction "B1_NEG_NEG_1") (pintype "bidirectional"))
      (node (ref "C7") (pin "-") (pinfunction "-_-") (pintype "passive"))
      (node (ref "C9") (pin "-") (pinfunction "-_-") (pintype "passive"))
      (node (ref "ON/OFF") (pin "2") (pinfunction "S_2") (pintype "passive"))
    )
    (net (code "19") (name "B1_TO_LOAD") (class "Default")
      (node (ref "D1") (pin "A") (pinfunction "A_A") (pintype "passive"))
      (node (ref "ON/OFF") (pin "5") (pinfunction "S_5") (pintype "passive"))
    )
    (net (code "20") (name "B2_CELL1") (class "Default")
      (node (ref "B2_CHRG_CONTROLLER") (pin "2") (pinfunction "2_2") (pintype "passive"))
      (node (ref "B2_CONN_EXTRA") (pin "2") (pinfunction "2_2") (pintype "passive"))
    )
    (net (code "21") (name "B2_CELL2") (class "Default")
      (node (ref "B2_CHRG_CONTROLLER") (pin "3") (pinfunction "3_3") (pintype "passive"))
      (node (ref "B2_CONN_EXTRA") (pin "3") (pinfunction "3_3") (pintype "passive"))
    )
    (net (code "22") (name "B2_CHRG_IN") (class "Default")
      (node (ref "B2CC") (pin "6") (pinfunction "6_6") (pintype "passive"))
      (node (ref "B2_CHRG_CONTROLLER") (pin "4") (pinfunction "4_4") (pintype "passive"))
      (node (ref "C10") (pin "+") (pinfunction "+_+") (pintype "passive"))
      (node (ref "C8") (pin "+") (pinfunction "+_+") (pintype "passive"))
    )
    (net (code "23") (name "B2_CHRG_OUT") (class "Default")
      (node (ref "B2CC") (pin "5") (pinfunction "5_5") (pintype "passive"))
      (node (ref "ON/OFF") (pin "3") (pinfunction "S_3") (pintype "passive"))
    )
    (net (code "24") (name "B2_GND") (class "Default")
      (node (ref "B2_CHRG_CONTROLLER") (pin "1") (pinfunction "1_1") (pintype "passive"))
      (node (ref "B2_CONN_EXTRA") (pin "1") (pinfunction "1_1") (pintype "passive"))
      (node (ref "C10") (pin "-") (pinfunction "-_-") (pintype "passive"))
      (node (ref "C8") (pin "-") (pinfunction "-_-") (pintype "passive"))
      (node (ref "ON/OFF") (pin "4") (pinfunction "S_4") (pintype "passive"))
    )
    (net (code "25") (name "B2_TO_LOAD") (class "Default")
      (node (ref "D2") (pin "A") (pinfunction "A_A") (pintype "passive"))
      (node (ref "ON/OFF") (pin "7") (pinfunction "S_7") (pintype "passive"))
    )
    (net (code "26") (name "BATT_1_TS1") (class "Default")
      (node (ref "ARD_3") (pin "1") (pinfunction "1_1") (pintype "passive"))
      (node (ref "B_T/S") (pin "1") (pinfunction "S_1") (pintype "passive"))
      (node (ref "R30") (pin "1") (pinfunction "1_1") (pintype "passive"))
      (node (ref "R31") (pin "2") (pinfunction "2_2") (pintype "passive"))
    )
    (net (code "27") (name "BATT_1_TS2") (class "Default")
      (node (ref "ARD_3") (pin "2") (pinfunction "2_2") (pintype "passive"))
      (node (ref "B_T/S") (pin "3") (pinfunction "S_3") (pintype "passive"))
      (node (ref "R32") (pin "1") (pinfunction "1_1") (pintype "passive"))
      (node (ref "R33") (pin "2") (pinfunction "2_2") (pintype "passive"))
    )
    (net (code "28") (name "BATT_2_TS1") (class "Default")
      (node (ref "ARD_3") (pin "3") (pinfunction "3_3") (pintype "passive"))
      (node (ref "B_T/S") (pin "4") (pinfunction "S_4") (pintype "passive"))
      (node (ref "R35") (pin "1") (pinfunction "1_1") (pintype "passive"))
      (node (ref "R36") (pin "2") (pinfunction "2_2") (pintype "passive"))
    )
    (net (code "29") (name "BATT_2_TS2") (class "Default")
      (node (ref "ARD_3") (pin "4") (pinfunction "4_4") (pintype "passive"))
      (node (ref "B_T/S") (pin "6") (pinfunction "S_6") (pintype "passive"))
      (node (ref "R37") (pin "1") (pinfunction "1_1") (pintype "passive"))
      (node (ref "R38") (pin "2") (pinfunction "2_2") (pintype "passive"))
    )
    (net (code "30") (name "BATT_CHRG_PWR") (class "Default")
      (node (ref "B1_CHRG_CONTROLLER") (pin "5") (pinfunction "5_5") (pintype "passive"))
      (node (ref "B2_CHRG_CONTROLLER") (pin "5") (pinfunction "5_5") (pintype "passive"))
      (node (ref "MPPT") (pin "1") (pinfunction "S_1") (pintype "passive"))
    )
    (net (code "31") (name "BATT_CHRG_PWR_RTN") (class "Default")
      (node (ref "B1_CHRG_CONTROLLER") (pin "6") (pinfunction "6_6") (pintype "passive"))
      (node (ref "B2_CHRG_CONTROLLER") (pin "6") (pinfunction "6_6") (pintype "passive"))
      (node (ref "MPPT") (pin "2") (pinfunction "S_2") (pintype "passive"))
    )
    (net (code "32") (name "BATT_EXT_PWR") (class "Default")
      (node (ref "BATT_EXT") (pin "POS") (pinfunction "POS_POS") (pintype "bidirectional"))
      (node (ref "B_EXT") (pin "1") (pinfunction "S_1") (pintype "passive"))
      (node (ref "C2_PWR") (pin "1") (pinfunction "1_1") (pintype "passive"))
      (node (ref "C2_PWR") (pin "3") (pinfunction "3_3") (pintype "passive"))
      (node (ref "PEXT1") (pin "1") (pinfunction "P_1") (pintype "passive"))
      (node (ref "PEXT2") (pin "1") (pinfunction "P_1") (pintype "passive"))
      (node (ref "PEXT3") (pin "1") (pinfunction "P_1") (pintype "passive"))
    )
    (net (code "33") (name "CANRX") (class "Default")
      (node (ref "ARD_3") (pin "7") (pinfunction "7_7") (pintype "passive"))
    )
    (net (code "34") (name "CANTX") (class "Default")
      (node (ref "ARD_3") (pin "8") (pinfunction "8_8") (pintype "passive"))
    )
    (net (code "35") (name "CHIP_SEL") (class "Default")
      (node (ref "ARD_7") (pin "8") (pinfunction "8_8") (pintype "passive"))
    )
    (net (code "36") (name "CTS") (class "Default")
      (node (ref "RB1") (pin "5") (pinfunction "5_5") (pintype "passive"))
    )
    (net (code "37") (name "CUTDOWN_1_FIRE") (class "Default")
      (node (ref "ARD_6") (pin "5") (pinfunction "5_5") (pintype "passive"))
      (node (ref "R1") (pin "2") (pinfunction "2_2") (pintype "passive"))
    )
    (net (code "38") (name "CUTDOWN_2_FIRE") (class "Default")
      (node (ref "ARD_6") (pin "4") (pinfunction "4_4") (pintype "passive"))
      (node (ref "R4") (pin "2") (pinfunction "2_2") (pintype "passive"))
    )
    (net (code "39") (name "C_GND") (class "Default")
      (node (ref "C1_TLM") (pin "12") (pinfunction "12_12") (pintype "passive"))
      (node (ref "EEPROM1") (pin "4") (pinfunction "VSS_4") (pintype "bidirectional"))
      (node (ref "R20") (pin "1") (pinfunction "1_1") (pintype "passive"))
    )
    (net (code "40") (name "C_ID1") (class "Default")
      (node (ref "ARD_8") (pin "4") (pinfunction "4_4") (pintype "passive"))
      (node (ref "C1_TLM") (pin "8") (pinfunction "8_8") (pintype "passive"))
    )
    (net (code "41") (name "C_ID2") (class "Default")
      (node (ref "ARD_8") (pin "6") (pinfunction "6_6") (pintype "passive"))
      (node (ref "C1_TLM") (pin "9") (pinfunction "9_9") (pintype "passive"))
    )
    (net (code "42") (name "C_ID3") (class "Default")
      (node (ref "ARD_9") (pin "6") (pinfunction "6_6") (pintype "passive"))
      (node (ref "C1_TLM") (pin "10") (pinfunction "10_10") (pintype "passive"))
    )
    (net (code "43") (name "C_ID4") (class "Default")
      (node (ref "C1_TLM") (pin "11") (pinfunction "11_11") (pintype "passive"))
      (node (ref "R20") (pin "2") (pinfunction "2_2") (pintype "passive"))
    )
    (net (code "44") (name "C_PWR{slash}MODE") (class "Default")
      (node (ref "C1_TLM") (pin "6") (pinfunction "6_6") (pintype "passive"))
    )
    (net (code "45") (name "C_SCL") (class "Default")
      (node (ref "C1_TLM") (pin "14") (pinfunction "14_14") (pintype "passive"))
      (node (ref "EEPROM1") (pin "6") (pinfunction "SCL_6") (pintype "bidirectional"))
    )
    (net (code "46") (name "C_SDA") (class "Default")
      (node (ref "C1_TLM") (pin "13") (pinfunction "13_13") (pintype "passive"))
      (node (ref "EEPROM1") (pin "5") (pinfunction "SDA_5") (pintype "bidirectional"))
    )
    (net (code "47") (name "C_SWITCH") (class "Default")
      (node (ref "ARD_8") (pin "2") (pinfunction "2_2") (pintype "passive"))
    )
    (net (code "48") (name "C_TRIG") (class "Default")
      (node (ref "ARD_8") (pin "3") (pinfunction "3_3") (pintype "passive"))
      (node (ref "C1_TLM") (pin "7") (pinfunction "7_7") (pintype "passive"))
    )
    (net (code "49") (name "D2") (class "Default")
      (node (ref "ARD_6") (pin "6") (pinfunction "6_6") (pintype "passive"))
    )
    (net (code "50") (name "D6") (class "Default")
      (node (ref "ARD_6") (pin "2") (pinfunction "2_2") (pintype "passive"))
    )
    (net (code "51") (name "D7") (class "Default")
      (node (ref "ARD_6") (pin "1") (pinfunction "1_1") (pintype "passive"))
    )
    (net (code "52") (name "D9") (class "Default")
      (node (ref "ARD_7") (pin "9") (pinfunction "9_9") (pintype "passive"))
    )
    (net (code "53") (name "D29") (class "Default")
      (node (ref "ARD_9") (pin "5") (pinfunction "5_5") (pintype "passive"))
    )
    (net (code "54") (name "D33") (class "Default")
      (node (ref "ARD_9") (pin "7") (pinfunction "7_7") (pintype "passive"))
    )
    (net (code "55") (name "D35") (class "Default")
      (node (ref "ARD_9") (pin "8") (pinfunction "8_8") (pintype "passive"))
    )
    (net (code "56") (name "D37") (class "Default")
      (node (ref "ARD_9") (pin "9") (pinfunction "9_9") (pintype "passive"))
    )
    (net (code "57") (name "D39") (class "Default")
      (node (ref "ARD_9") (pin "10") (pinfunction "10_10") (pintype "passive"))
    )
    (net (code "58") (name "D40") (class "Default")
      (node (ref "ARD_8") (pin "11") (pinfunction "11_11") (pintype "passive"))
    )
    (net (code "59") (name "D41") (class "Default")
      (node (ref "ARD_9") (pin "11") (pinfunction "11_11") (pintype "passive"))
    )
    (net (code "60") (name "D42") (class "Default")
      (node (ref "ARD_8") (pin "12") (pinfunction "12_12") (pintype "passive"))
    )
    (net (code "61") (name "D43") (class "Default")
      (node (ref "ARD_9") (pin "12") (pinfunction "12_12") (pintype "passive"))
    )
    (net (code "62") (name "D44") (class "Default")
      (node (ref "ARD_8") (pin "13") (pinfunction "13_13") (pintype "passive"))
    )
    (net (code "63") (name "D45") (class "Default")
      (node (ref "ARD_9") (pin "13") (pinfunction "13_13") (pintype "passive"))
    )
    (net (code "64") (name "D46") (class "Default")
      (node (ref "ARD_8") (pin "14") (pinfunction "14_14") (pintype "passive"))
    )
    (net (code "65") (name "D47") (class "Default")
      (node (ref "ARD_9") (pin "14") (pinfunction "14_14") (pintype "passive"))
    )
    (net (code "66") (name "D48") (class "Default")
      (node (ref "ARD_8") (pin "15") (pinfunction "15_15") (pintype "passive"))
    )
    (net (code "67") (name "D49") (class "Default")
      (node (ref "ARD_9") (pin "15") (pinfunction "15_15") (pintype "passive"))
    )
    (net (code "68") (name "D50") (class "Default")
      (node (ref "ARD_8") (pin "16") (pinfunction "16_16") (pintype "passive"))
    )
    (net (code "69") (name "D51") (class "Default")
      (node (ref "ARD_9") (pin "16") (pinfunction "16_16") (pintype "passive"))
    )
    (net (code "70") (name "D52") (class "Default")
      (node (ref "ARD_8") (pin "17") (pinfunction "17_17") (pintype "passive"))
    )
    (net (code "71") (name "D53") (class "Default")
      (node (ref "ARD_9") (pin "17") (pinfunction "17_17") (pintype "passive"))
    )
    (net (code "72") (name "DAC0") (class "Default")
      (node (ref "ARD_3") (pin "5") (pinfunction "5_5") (pintype "passive"))
    )
    (net (code "73") (name "DAC1") (class "Default")
      (node (ref "ARD_3") (pin "6") (pinfunction "6_6") (pintype "passive"))
    )
    (net (code "74") (name "FLT_CMP_TEMP") (class "Default")
      (node (ref "ARD_2") (pin "7") (pinfunction "7_7") (pintype "passive"))
      (node (ref "FLT_CMP_TEMP") (pin "1") (pinfunction "1_1") (pintype "passive"))
      (node (ref "R26") (pin "1") (pinfunction "1_1") (pintype "passive"))
      (node (ref "R27") (pin "2") (pinfunction "2_2") (pintype "passive"))
    )
    (net (code "75") (name "GND") (class "Default")
      (node (ref "ALT") (pin "3") (pinfunction "3_3") (pintype "passive"))
      (node (ref "ARD_1") (pin "6") (pinfunction "6_6") (pintype "passive"))
      (node (ref "ARD_1") (pin "7") (pinfunction "7_7") (pintype "passive"))
      (node (ref "ARD_4") (pin "6") (pinfunction "6_6") (pintype "passive"))
      (node (ref "ARD_7") (pin "4") (pinfunction "4_4") (pintype "passive"))
      (node (ref "ARD_8") (pin "18") (pinfunction "18_18") (pintype "passive"))
      (node (ref "ARD_9") (pin "18") (pinfunction "18_18") (pintype "passive"))
      (node (ref "B1CC") (pin "2") (pinfunction "2_2") (pintype "passive"))
      (node (ref "B2CC") (pin "2") (pinfunction "2_2") (pintype "passive"))
      (node (ref "BATT_EXT") (pin "NEG") (pinfunction "NEG_NEG") (pintype "bidirectional"))
      (node (ref "B_EXT") (pin "2") (pinfunction "S_2") (pintype "passive"))
      (node (ref "B_T/S") (pin "2") (pinfunction "S_2") (pintype "passive"))
      (node (ref "B_T/S") (pin "5") (pinfunction "S_5") (pintype "passive"))
      (node (ref "C1") (pin "2") (pinfunction "2_2") (pintype "passive"))
      (node (ref "C1_TLM") (pin "15") (pinfunction "15_15") (pintype "passive"))
      (node (ref "C1_TLM") (pin "2") (pinfunction "2_2") (pintype "passive"))
      (node (ref "C1_TLM") (pin "4") (pinfunction "4_4") (pintype "passive"))
      (node (ref "C2_PWR") (pin "2") (pinfunction "2_2") (pintype "passive"))
      (node (ref "C2_PWR") (pin "4") (pinfunction "4_4") (pintype "passive"))
      (node (ref "CN3") (pin "4") (pinfunction "4_4") (pintype "bidirectional"))
      (node (ref "FLT_CMP_TMP_NEG") (pin "1") (pinfunction "1_1") (pintype "passive"))
      (node (ref "GPS") (pin "8") (pinfunction "8_8") (pintype "passive"))
      (node (ref "LCC") (pin "2") (pinfunction "2_2") (pintype "passive"))
      (node (ref "ON/OFF") (pin "10") (pinfunction "S_10") (pintype "passive"))
      (node (ref "ON/OFF") (pin "6") (pinfunction "S_6") (pintype "passive"))
      (node (ref "ON/OFF") (pin "8") (pinfunction "S_8") (pintype "passive"))
      (node (ref "Q1") (pin "E") (pinfunction "E_E") (pintype "passive"))
      (node (ref "Q2") (pin "E") (pinfunction "E_E") (pintype "passive"))
      (node (ref "Q3") (pin "E") (pinfunction "E_E") (pintype "passive"))
      (node (ref "Q4") (pin "E") (pinfunction "E_E") (pintype "passive"))
      (node (ref "Q5") (pin "E") (pinfunction "E_E") (pintype "passive"))
      (node (ref "Q6") (pin "E") (pinfunction "E_E") (pintype "passive"))
      (node (ref "Q7") (pin "E") (pinfunction "E_E") (pintype "passive"))
      (node (ref "R12") (pin "1") (pinfunction "1_1") (pintype "passive"))
      (node (ref "R13") (pin "1") (pinfunction "1_1") (pintype "passive"))
      (node (ref "R15") (pin "1") (pinfunction "1_1") (pintype "passive"))
      (node (ref "R18") (pin "1") (pinfunction "1_1") (pintype "passive"))
      (node (ref "R19") (pin "1") (pinfunction "1_1") (pintype "passive"))
      (node (ref "R23") (pin "1") (pinfunction "1_1") (pintype "passive"))
      (node (ref "R25") (pin "1") (pinfunction "1_1") (pintype "passive"))
      (node (ref "R27") (pin "1") (pinfunction "1_1") (pintype "passive"))
      (node (ref "R3") (pin "1") (pinfunction "1_1") (pintype "passive"))
      (node (ref "R31") (pin "1") (pinfunction "1_1") (pintype "passive"))
      (node (ref "R33") (pin "1") (pinfunction "1_1") (pintype "passive"))
      (node (ref "R36") (pin "1") (pinfunction "1_1") (pintype "passive"))
      (node (ref "R38") (pin "1") (pinfunction "1_1") (pintype "passive"))
      (node (ref "R8") (pin "1") (pinfunction "1_1") (pintype "passive"))
      (node (ref "R9") (pin "1") (pinfunction "1_1") (pintype "passive"))
      (node (ref "RB1") (pin "6") (pinfunction "6_6") (pintype "passive"))
      (node (ref "RB2") (pin "1") (pinfunction "1_1") (pintype "passive"))
      (node (ref "RB2") (pin "8") (pinfunction "8_8") (pintype "passive"))
      (node (ref "SACC") (pin "2") (pinfunction "2_2") (pintype "passive"))
      (node (ref "X12") (pin "4") (pinfunction "GND_4") (pintype "power_in"))
    )
    (net (code "76") (name "GYRO_PWR") (class "Default")
      (node (ref "ARD_8") (pin "5") (pinfunction "5_5") (pintype "passive"))
      (node (ref "CN3") (pin "3") (pinfunction "3_3") (pintype "bidirectional"))
    )
    (net (code "77") (name "HEATER_1_PWR") (class "Default")
      (node (ref "C3_CMD") (pin "8") (pinfunction "8_8") (pintype "passive"))
      (node (ref "H1") (pin "1") (pinfunction "S_1") (pintype "passive"))
      (node (ref "PO4") (pin "1") (pinfunction "P_1") (pintype "passive"))
    )
    (net (code "78") (name "HEATER_1_PWR_RTN") (class "Default")
      (node (ref "C3_CMD") (pin "9") (pinfunction "9_9") (pintype "passive"))
      (node (ref "H1") (pin "2") (pinfunction "S_2") (pintype "passive"))
      (node (ref "Q4") (pin "C") (pinfunction "C_C") (pintype "passive"))
    )
    (net (code "79") (name "HEATER_2_PWR") (class "Default")
      (node (ref "C3_CMD") (pin "10") (pinfunction "10_10") (pintype "passive"))
      (node (ref "H2") (pin "1") (pinfunction "S_1") (pintype "passive"))
      (node (ref "PO5") (pin "1") (pinfunction "P_1") (pintype "passive"))
    )
    (net (code "80") (name "HEATER_2_PWR_RTN") (class "Default")
      (node (ref "C3_CMD") (pin "11") (pinfunction "11_11") (pintype "passive"))
      (node (ref "H2") (pin "2") (pinfunction "S_2") (pintype "passive"))
      (node (ref "Q5") (pin "C") (pinfunction "C_C") (pintype "passive"))
    )
    (net (code "81") (name "HEATER_CONTROL_1") (class "Default")
      (node (ref "ARD_7") (pin "10") (pinfunction "10_10") (pintype "passive"))
      (node (ref "R10") (pin "2") (pinfunction "2_2") (pintype "passive"))
    )
    (net (code "82") (name "HEATER_CONTROL_2") (class "Default")
      (node (ref "ARD_6") (pin "3") (pinfunction "3_3") (pintype "passive"))
      (node (ref "R11") (pin "2") (pinfunction "2_2") (pintype "passive"))
    )
    (net (code "83") (name "IOREF") (class "Default")
      (node (ref "ARD_1") (pin "2") (pinfunction "2_2") (pintype "passive"))
    )
    (net (code "84") (name "LI_ION") (class "Default")
      (node (ref "RB2") (pin "7") (pinfunction "7_7") (pintype "passive"))
    )
    (net (code "85") (name "LOAD_IN") (class "Default")
      (node (ref "D1") (pin "C") (pinfunction "C_C") (pintype "passive"))
      (node (ref "D2") (pin "C") (pinfunction "C_C") (pintype "passive"))
      (node (ref "LCC") (pin "6") (pinfunction "6_6") (pintype "passive"))
    )
    (net (code "86") (name "MISO") (class "Default")
      (node (ref "ARD_4") (pin "1") (pinfunction "1_1") (pintype "passive"))
      (node (ref "ARD_7") (pin "6") (pinfunction "6_6") (pintype "passive"))
    )
    (net (code "87") (name "MOSI") (class "Default")
      (node (ref "ARD_4") (pin "4") (pinfunction "4_4") (pintype "passive"))
      (node (ref "ARD_7") (pin "7") (pinfunction "7_7") (pintype "passive"))
    )
    (net (code "88") (name "NET_AV") (class "Default")
      (node (ref "RB2") (pin "5") (pinfunction "5_5") (pintype "passive"))
    )
    (net (code "89") (name "Net-(Q4-PadB)") (class "Default")
      (node (ref "Q4") (pin "B") (pinfunction "B_B") (pintype "passive"))
      (node (ref "R10") (pin "1") (pinfunction "1_1") (pintype "passive"))
      (node (ref "R12") (pin "2") (pinfunction "2_2") (pintype "passive"))
    )
    (net (code "90") (name "Net-(Q5-PadB)") (class "Default")
      (node (ref "Q5") (pin "B") (pinfunction "B_B") (pintype "passive"))
      (node (ref "R11") (pin "1") (pinfunction "1_1") (pintype "passive"))
      (node (ref "R13") (pin "2") (pinfunction "2_2") (pintype "passive"))
    )
    (net (code "91") (name "Net-(Q6-PadB)") (class "Default")
      (node (ref "Q6") (pin "B") (pinfunction "B_B") (pintype "passive"))
      (node (ref "R16") (pin "1") (pinfunction "1_1") (pintype "passive"))
      (node (ref "R18") (pin "2") (pinfunction "2_2") (pintype "passive"))
    )
    (net (code "92") (name "Net-(Q7-PadB)") (class "Default")
      (node (ref "Q7") (pin "B") (pinfunction "B_B") (pintype "passive"))
      (node (ref "R17") (pin "1") (pinfunction "1_1") (pintype "passive"))
      (node (ref "R19") (pin "2") (pinfunction "2_2") (pintype "passive"))
    )
    (net (code "93") (name "Net-(T1-B)") (class "Default")
      (node (ref "R1") (pin "1") (pinfunction "1_1") (pintype "passive"))
      (node (ref "R2") (pin "2") (pinfunction "2_2") (pintype "passive"))
      (node (ref "T1") (pin "2") (pinfunction "B_2") (pintype "passive"))
    )
    (net (code "94") (name "Net-(T1-E)") (class "Default")
      (node (ref "Q1") (pin "B") (pinfunction "B_B") (pintype "passive"))
      (node (ref "R2") (pin "1") (pinfunction "1_1") (pintype "passive"))
      (node (ref "R3") (pin "2") (pinfunction "2_2") (pintype "passive"))
      (node (ref "T1") (pin "3") (pinfunction "E_3") (pintype "passive"))
    )
    (net (code "95") (name "Net-(T2-B)") (class "Default")
      (node (ref "R4") (pin "1") (pinfunction "1_1") (pintype "passive"))
      (node (ref "R6") (pin "2") (pinfunction "2_2") (pintype "passive"))
      (node (ref "T2") (pin "2") (pinfunction "B_2") (pintype "passive"))
    )
    (net (code "96") (name "Net-(T2-E)") (class "Default")
      (node (ref "Q2") (pin "B") (pinfunction "B_B") (pintype "passive"))
      (node (ref "R6") (pin "1") (pinfunction "1_1") (pintype "passive"))
      (node (ref "R8") (pin "2") (pinfunction "2_2") (pintype "passive"))
      (node (ref "T2") (pin "3") (pinfunction "E_3") (pintype "passive"))
    )
    (net (code "97") (name "Net-(T3-B)") (class "Default")
      (node (ref "R5") (pin "1") (pinfunction "1_1") (pintype "passive"))
      (node (ref "R7") (pin "2") (pinfunction "2_2") (pintype "passive"))
      (node (ref "T3") (pin "2") (pinfunction "B_2") (pintype "passive"))
    )
    (net (code "98") (name "Net-(T3-E)") (class "Default")
      (node (ref "Q3") (pin "B") (pinfunction "B_B") (pintype "passive"))
      (node (ref "R7") (pin "1") (pinfunction "1_1") (pintype "passive"))
      (node (ref "R9") (pin "2") (pinfunction "2_2") (pintype "passive"))
      (node (ref "T3") (pin "3") (pinfunction "E_3") (pintype "passive"))
    )
    (net (code "99") (name "ON_OFF") (class "Default")
      (node (ref "RB2") (pin "6") (pinfunction "6_6") (pintype "passive"))
    )
    (net (code "100") (name "PYRO_1_PWR") (class "Default")
      (node (ref "C3_CMD") (pin "1") (pinfunction "1_1") (pintype "passive"))
      (node (ref "PO1") (pin "1") (pinfunction "P_1") (pintype "passive"))
      (node (ref "PYRO1") (pin "1") (pinfunction "S_1") (pintype "passive"))
    )
    (net (code "101") (name "PYRO_1_PWR_RTN") (class "Default")
      (node (ref "C3_CMD") (pin "2") (pinfunction "2_2") (pintype "passive"))
      (node (ref "PYRO1") (pin "2") (pinfunction "S_2") (pintype "passive"))
      (node (ref "Q1") (pin "C") (pinfunction "C_C") (pintype "passive"))
      (node (ref "T1") (pin "1") (pinfunction "C_1") (pintype "passive"))
    )
    (net (code "102") (name "PYRO_2_PWR") (class "Default")
      (node (ref "C3_CMD") (pin "3") (pinfunction "3_3") (pintype "passive"))
      (node (ref "PO2") (pin "1") (pinfunction "P_1") (pintype "passive"))
      (node (ref "PYRO2") (pin "1") (pinfunction "S_1") (pintype "passive"))
    )
    (net (code "103") (name "PYRO_2_PWR_RTN") (class "Default")
      (node (ref "C3_CMD") (pin "4") (pinfunction "4_4") (pintype "passive"))
      (node (ref "PYRO2") (pin "2") (pinfunction "S_2") (pintype "passive"))
      (node (ref "Q2") (pin "C") (pinfunction "C_C") (pintype "passive"))
      (node (ref "T2") (pin "1") (pinfunction "C_1") (pintype "passive"))
    )
    (net (code "104") (name "RESET") (class "Default")
      (node (ref "ARD_1") (pin "3") (pinfunction "3_3") (pintype "passive"))
      (node (ref "ARD_4") (pin "5") (pinfunction "5_5") (pintype "passive"))
      (node (ref "ON/OFF") (pin "9") (pinfunction "S_9") (pintype "passive"))
    )
    (net (code "105") (name "RF_IN") (class "Default")
      (node (ref "GPS") (pin "2") (pinfunction "2_2") (pintype "passive"))
    )
    (net (code "106") (name "RI") (class "Default")
      (node (ref "RB2") (pin "4") (pinfunction "4_4") (pintype "passive"))
    )
    (net (code "107") (name "RTS") (class "Default")
      (node (ref "RB1") (pin "1") (pinfunction "1_1") (pintype "passive"))
    )
    (net (code "108") (name "RX0") (class "Default")
      (node (ref "ARD_6") (pin "8") (pinfunction "8_8") (pintype "passive"))
      (node (ref "X12") (pin "2") (pinfunction "D-_2") (pintype "bidirectional"))
    )
    (net (code "109") (name "RX1") (class "Default")
      (node (ref "ARD_5") (pin "6") (pinfunction "6_6") (pintype "passive"))
      (node (ref "GPS") (pin "5") (pinfunction "5_5") (pintype "passive"))
    )
    (net (code "110") (name "RX2") (class "Default")
      (node (ref "ARD_5") (pin "4") (pinfunction "4_4") (pintype "passive"))
    )
    (net (code "111") (name "RX3") (class "Default")
      (node (ref "ARD_5") (pin "2") (pinfunction "2_2") (pintype "passive"))
      (node (ref "RB1") (pin "2") (pinfunction "2_2") (pintype "passive"))
    )
    (net (code "112") (name "RXB") (class "Default")
      (node (ref "GPS") (pin "7") (pinfunction "7_7") (pintype "passive"))
    )
    (net (code "113") (name "SCK") (class "Default")
      (node (ref "ARD_4") (pin "3") (pinfunction "3_3") (pintype "passive"))
      (node (ref "ARD_7") (pin "5") (pinfunction "5_5") (pintype "passive"))
    )
    (net (code "114") (name "SCL") (class "Default")
      (node (ref "ARD_5") (pin "8") (pinfunction "8_8") (pintype "passive"))
      (node (ref "B1CC") (pin "3") (pinfunction "3_3") (pintype "passive"))
      (node (ref "B2CC") (pin "3") (pinfunction "3_3") (pintype "passive"))
      (node (ref "CN3") (pin "1") (pinfunction "1_1") (pintype "bidirectional"))
      (node (ref "LCC") (pin "3") (pinfunction "3_3") (pintype "passive"))
      (node (ref "SACC") (pin "3") (pinfunction "3_3") (pintype "passive"))
    )
    (net (code "115") (name "SCL1") (class "Default")
      (node (ref "ARD_7") (pin "1") (pinfunction "1_1") (pintype "passive"))
    )
    (net (code "116") (name "SDA") (class "Default")
      (node (ref "ARD_5") (pin "7") (pinfunction "7_7") (pintype "passive"))
      (node (ref "B1CC") (pin "4") (pinfunction "4_4") (pintype "passive"))
      (node (ref "B2CC") (pin "4") (pinfunction "4_4") (pintype "passive"))
      (node (ref "CN3") (pin "2") (pinfunction "2_2") (pintype "bidirectional"))
      (node (ref "LCC") (pin "4") (pinfunction "4_4") (pintype "passive"))
      (node (ref "SACC") (pin "4") (pinfunction "4_4") (pintype "passive"))
    )
    (net (code "117") (name "SDA1") (class "Default")
      (node (ref "ARD_7") (pin "2") (pinfunction "2_2") (pintype "passive"))
    )
    (net (code "118") (name "SPARE_1_PWR") (class "Default")
      (node (ref "C3_CMD") (pin "12") (pinfunction "12_12") (pintype "passive"))
      (node (ref "PO6") (pin "1") (pinfunction "P_1") (pintype "passive"))
      (node (ref "SPRL1") (pin "1") (pinfunction "S_1") (pintype "passive"))
    )
    (net (code "119") (name "SPARE_1_PWR_RTN") (class "Default")
      (node (ref "C3_CMD") (pin "13") (pinfunction "13_13") (pintype "passive"))
      (node (ref "Q6") (pin "C") (pinfunction "C_C") (pintype "passive"))
      (node (ref "SPRL1") (pin "2") (pinfunction "S_2") (pintype "passive"))
    )
    (net (code "120") (name "SPARE_2_PWR") (class "Default")
      (node (ref "C3_CMD") (pin "14") (pinfunction "14_14") (pintype "passive"))
      (node (ref "PO7") (pin "1") (pinfunction "P_1") (pintype "passive"))
      (node (ref "SPRL2") (pin "1") (pinfunction "S_1") (pintype "passive"))
    )
    (net (code "121") (name "SPARE_2_PWR_RTN") (class "Default")
      (node (ref "C3_CMD") (pin "15") (pinfunction "15_15") (pintype "passive"))
      (node (ref "Q7") (pin "C") (pinfunction "C_C") (pintype "passive"))
      (node (ref "SPRL2") (pin "2") (pinfunction "S_2") (pintype "passive"))
    )
    (net (code "122") (name "SPARE_HIGH_1_CONTROL") (class "Default")
      (node (ref "ARD_9") (pin "2") (pinfunction "2_2") (pintype "passive"))
      (node (ref "R5") (pin "2") (pinfunction "2_2") (pintype "passive"))
    )
    (net (code "123") (name "SPARE_HIGH_1_PWR") (class "Default")
      (node (ref "C3_CMD") (pin "5") (pinfunction "5_5") (pintype "passive"))
      (node (ref "PO3") (pin "1") (pinfunction "P_1") (pintype "passive"))
      (node (ref "SPRH1") (pin "1") (pinfunction "S_1") (pintype "passive"))
    )
    (net (code "124") (name "SPARE_HIGH_1_PWR_RTN") (class "Default")
      (node (ref "C3_CMD") (pin "6") (pinfunction "6_6") (pintype "passive"))
      (node (ref "Q3") (pin "C") (pinfunction "C_C") (pintype "passive"))
      (node (ref "SPRH1") (pin "2") (pinfunction "S_2") (pintype "passive"))
      (node (ref "T3") (pin "1") (pinfunction "C_1") (pintype "passive"))
    )
    (net (code "125") (name "SPARE_LOW_1_CONTROL") (class "Default")
      (node (ref "ARD_9") (pin "3") (pinfunction "3_3") (pintype "passive"))
      (node (ref "R16") (pin "2") (pinfunction "2_2") (pintype "passive"))
    )
    (net (code "126") (name "SPARE_LOW_2_CONTROL") (class "Default")
      (node (ref "ARD_9") (pin "4") (pinfunction "4_4") (pintype "passive"))
      (node (ref "R17") (pin "2") (pinfunction "2_2") (pintype "passive"))
    )
    (net (code "127") (name "S{slash}A_PWR_IN") (class "Default")
      (node (ref "C2_PWR") (pin "10") (pinfunction "10_10") (pintype "passive"))
      (node (ref "C2_PWR") (pin "6") (pinfunction "6_6") (pintype "passive"))
      (node (ref "C2_PWR") (pin "8") (pinfunction "8_8") (pintype "passive"))
      (node (ref "SACC") (pin "6") (pinfunction "6_6") (pintype "passive"))
    )
    (net (code "128") (name "S{slash}A_PWR_OUT") (class "Default")
      (node (ref "MPPT") (pin "3") (pinfunction "S_3") (pintype "passive"))
      (node (ref "SACC") (pin "5") (pinfunction "5_5") (pintype "passive"))
    )
    (net (code "129") (name "S{slash}A_PWR_RTN") (class "Default")
      (node (ref "C2_PWR") (pin "11") (pinfunction "11_11") (pintype "passive"))
      (node (ref "C2_PWR") (pin "7") (pinfunction "7_7") (pintype "passive"))
      (node (ref "C2_PWR") (pin "9") (pinfunction "9_9") (pintype "passive"))
      (node (ref "MPPT") (pin "4") (pinfunction "S_4") (pintype "passive"))
    )
    (net (code "130") (name "TEMP_EXT_1") (class "Default")
      (node (ref "ARD_2") (pin "8") (pinfunction "8_8") (pintype "passive"))
      (node (ref "C1_TLM") (pin "1") (pinfunction "1_1") (pintype "passive"))
      (node (ref "R22") (pin "1") (pinfunction "1_1") (pintype "passive"))
      (node (ref "R23") (pin "2") (pinfunction "2_2") (pintype "passive"))
    )
    (net (code "131") (name "TEMP_EXT_2") (class "Default")
      (node (ref "ARD_2") (pin "6") (pinfunction "6_6") (pintype "passive"))
      (node (ref "C1_TLM") (pin "3") (pinfunction "3_3") (pintype "passive"))
      (node (ref "R24") (pin "1") (pinfunction "1_1") (pintype "passive"))
      (node (ref "R25") (pin "2") (pinfunction "2_2") (pintype "passive"))
    )
    (net (code "132") (name "TX0") (class "Default")
      (node (ref "ARD_6") (pin "7") (pinfunction "7_7") (pintype "passive"))
      (node (ref "X12") (pin "3") (pinfunction "D+_3") (pintype "bidirectional"))
    )
    (net (code "133") (name "TX1") (class "Default")
      (node (ref "ARD_5") (pin "5") (pinfunction "5_5") (pintype "passive"))
      (node (ref "GPS") (pin "4") (pinfunction "4_4") (pintype "passive"))
    )
    (net (code "134") (name "TX2") (class "Default")
      (node (ref "ARD_5") (pin "3") (pinfunction "3_3") (pintype "passive"))
    )
    (net (code "135") (name "TX3") (class "Default")
      (node (ref "ARD_5") (pin "1") (pinfunction "1_1") (pintype "passive"))
      (node (ref "RB1") (pin "3") (pinfunction "3_3") (pintype "passive"))
    )
    (net (code "136") (name "TXB") (class "Default")
      (node (ref "GPS") (pin "6") (pinfunction "6_6") (pintype "passive"))
    )
    (net (code "137") (name "UNKNOWN") (class "Default")
      (node (ref "ARD_1") (pin "1") (pinfunction "1_1") (pintype "passive"))
    )
    (net (code "138") (name "VBAT") (class "Default")
      (node (ref "GPS") (pin "3") (pinfunction "3_3") (pintype "passive"))
    )
    (net (code "139") (name "VCC_RB") (class "Default")
      (node (ref "RB1") (pin "4") (pinfunction "4_4") (pintype "passive"))
    )
    (net (code "140") (name "VIN") (class "Default")
      (node (ref "ARD_1") (pin "8") (pinfunction "8_8") (pintype "passive"))
      (node (ref "LCC") (pin "5") (pinfunction "5_5") (pintype "passive"))
      (node (ref "PVIN1") (pin "1") (pinfunction "P_1") (pintype "passive"))
      (node (ref "PVIN2") (pin "1") (pinfunction "P_1") (pintype "passive"))
      (node (ref "PVIN3") (pin "1") (pinfunction "P_1") (pintype "passive"))
      (node (ref "PVIN4") (pin "1") (pinfunction "P_1") (pintype "passive"))
      (node (ref "PVIN5") (pin "1") (pinfunction "P_1") (pintype "passive"))
      (node (ref "PVIN6") (pin "1") (pinfunction "P_1") (pintype "passive"))
      (node (ref "PVIN7") (pin "1") (pinfunction "P_1") (pintype "passive"))
      (node (ref "R14") (pin "2") (pinfunction "2_2") (pintype "passive"))
    )
    (net (code "141") (name "VIN_VOLTAGE_TLM") (class "Default")
      (node (ref "ARD_2") (pin "4") (pinfunction "4_4") (pintype "passive"))
      (node (ref "C1") (pin "1") (pinfunction "1_1") (pintype "passive"))
      (node (ref "R14") (pin "1") (pinfunction "1_1") (pintype "passive"))
      (node (ref "R15") (pin "2") (pinfunction "2_2") (pintype "passive"))
    )
    (net (code "142") (name "unconnected-(ALT-Pad8)") (class "Default")
      (node (ref "ALT") (pin "8") (pinfunction "8_8") (pintype "passive"))
    )
    (net (code "143") (name "unconnected-(C1_TLM-Pad5)") (class "Default")
      (node (ref "C1_TLM") (pin "5") (pinfunction "5_5") (pintype "passive"))
    )
    (net (code "144") (name "unconnected-(C2_PWR-Pad5)") (class "Default")
      (node (ref "C2_PWR") (pin "5") (pinfunction "5_5") (pintype "passive"))
    )
    (net (code "145") (name "unconnected-(C2_PWR-Pad12)") (class "Default")
      (node (ref "C2_PWR") (pin "12") (pinfunction "12_12") (pintype "passive"))
    )
    (net (code "146") (name "unconnected-(C2_PWR-Pad13)") (class "Default")
      (node (ref "C2_PWR") (pin "13") (pinfunction "13_13") (pintype "passive"))
    )
    (net (code "147") (name "unconnected-(C2_PWR-Pad14)") (class "Default")
      (node (ref "C2_PWR") (pin "14") (pinfunction "14_14") (pintype "passive"))
    )
    (net (code "148") (name "unconnected-(C2_PWR-Pad15)") (class "Default")
      (node (ref "C2_PWR") (pin "15") (pinfunction "15_15") (pintype "passive"))
    )
    (net (code "149") (name "unconnected-(C3_CMD-Pad7)") (class "Default")
      (node (ref "C3_CMD") (pin "7") (pinfunction "7_7") (pintype "passive"))
    )
    (net (code "150") (name "unconnected-(EEPROM1-A0-Pad1)") (class "Default")
      (node (ref "EEPROM1") (pin "1") (pinfunction "A0_1") (pintype "bidirectional"))
    )
    (net (code "151") (name "unconnected-(EEPROM1-A1-Pad2)") (class "Default")
      (node (ref "EEPROM1") (pin "2") (pinfunction "A1_2") (pintype "bidirectional"))
    )
    (net (code "152") (name "unconnected-(EEPROM1-A2-Pad3)") (class "Default")
      (node (ref "EEPROM1") (pin "3") (pinfunction "A2_3") (pintype "bidirectional"))
    )
    (net (code "153") (name "unconnected-(EEPROM1-WP-Pad7)") (class "Default")
      (node (ref "EEPROM1") (pin "7") (pinfunction "WP_7") (pintype "bidirectional"))
    )
  )
)
